# ZX_UNO_0_15.net
KiCad netlist of a schematic drawn in Altium Designer
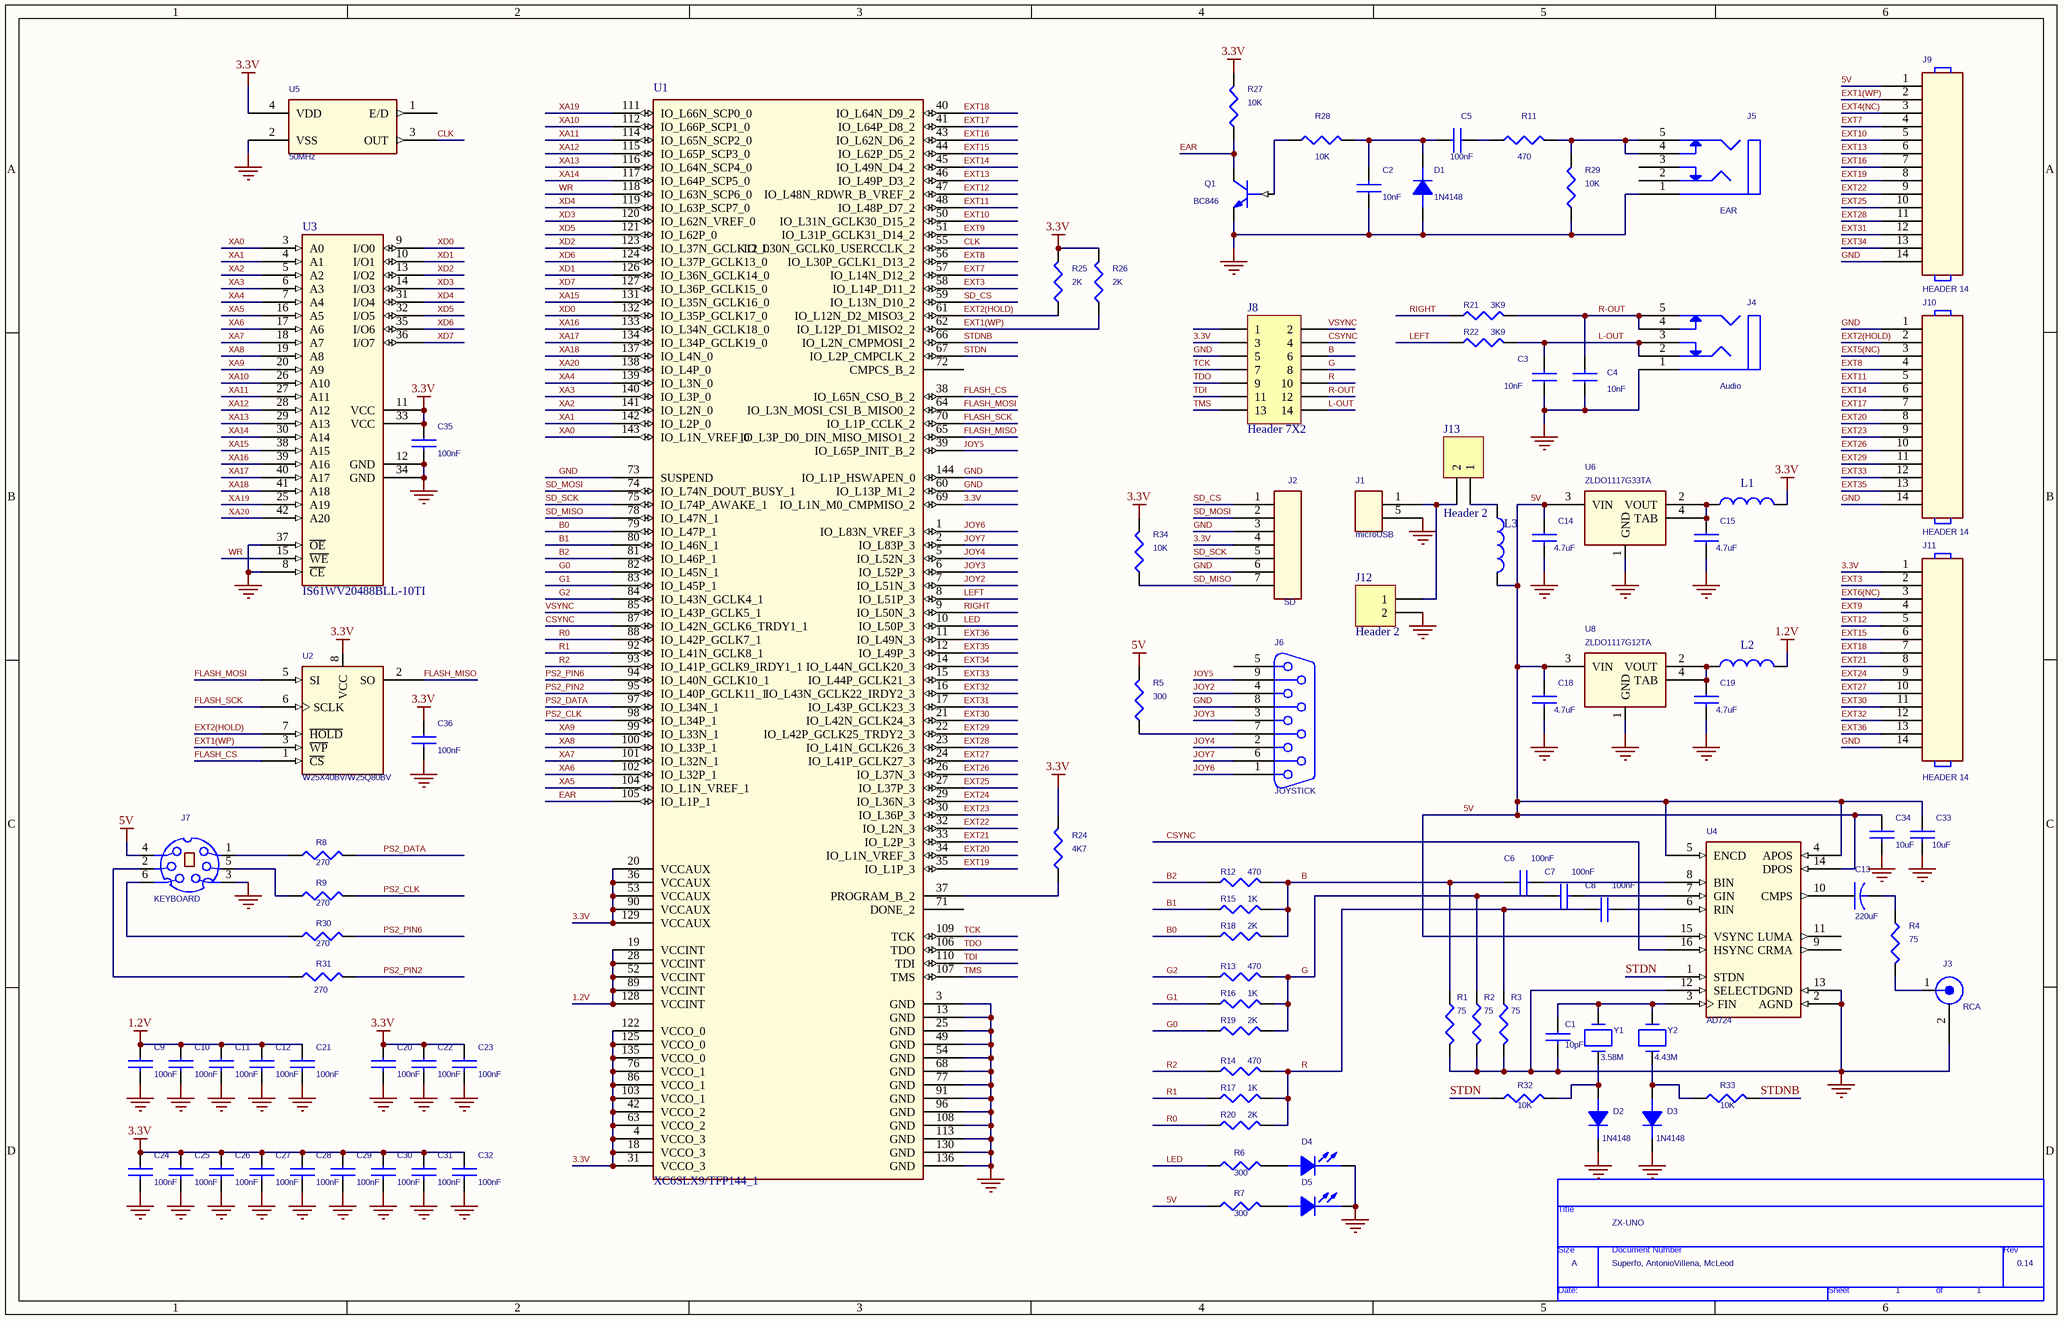
[diagram p0: ZX_UNO_0_15.SchDoc]

(export (version "E")
  (design (tool "Eeschema 10.0.6"))
  (components
    (comp (ref "*")
      (value "TitleBlock0")
      (fields
        (field (name "PAGE COUNT") "1")
        (field (name "PAGE NUMBER") "1")
        (field (name "PAGE SIZE") "A")
        (field (name "TITLE") "ZX-UNO")
        (field (name "REVCODE") "0.14")
        (field (name "DOC") "Superfo, AntonioVillena, McLeod")
      )
      (libsource (lib "*") (part "TitleBlock0"))
    )
    (comp (ref "C1") (value "10pF") (libsource (lib "*") (part "CAP NP_Dup1")))
    (comp (ref "C2") (value "10nF") (libsource (lib "*") (part "CAP NP_Dup1")))
    (comp (ref "C3") (value "10nF") (libsource (lib "*") (part "CAP NP_Dup1")))
    (comp (ref "C4") (value "10nF") (libsource (lib "*") (part "CAP NP_Dup1")))
    (comp (ref "C5") (value "100nF") (libsource (lib "*") (part "CAP NP_Dup1")))
    (comp (ref "C6") (value "100nF") (libsource (lib "*") (part "CAP NP_Dup1")))
    (comp (ref "C7") (value "100nF") (libsource (lib "*") (part "CAP NP_Dup1")))
    (comp (ref "C8") (value "100nF") (libsource (lib "*") (part "CAP NP_Dup1")))
    (comp (ref "C9") (value "100nF") (libsource (lib "*") (part "CAP NP")))
    (comp (ref "C10") (value "100nF") (libsource (lib "*") (part "CAP NP")))
    (comp (ref "C11") (value "100nF") (libsource (lib "*") (part "CAP NP")))
    (comp (ref "C12") (value "100nF") (libsource (lib "*") (part "CAP NP")))
    (comp (ref "C13") (value "220uF") (libsource (lib "*") (part "CAP")))
    (comp (ref "C14") (value "4.7uF") (libsource (lib "*") (part "CAP NP")))
    (comp (ref "C15") (value "4.7uF") (libsource (lib "*") (part "CAP NP")))
    (comp (ref "C18") (value "4.7uF") (libsource (lib "*") (part "CAP NP")))
    (comp (ref "C19") (value "4.7uF") (libsource (lib "*") (part "CAP NP")))
    (comp (ref "C20") (value "100nF") (libsource (lib "*") (part "CAP NP")))
    (comp (ref "C21") (value "100nF") (libsource (lib "*") (part "CAP NP")))
    (comp (ref "C22") (value "100nF") (libsource (lib "*") (part "CAP NP")))
    (comp (ref "C23") (value "100nF") (libsource (lib "*") (part "CAP NP")))
    (comp (ref "C24") (value "100nF") (libsource (lib "*") (part "CAP NP")))
    (comp (ref "C25") (value "100nF") (libsource (lib "*") (part "CAP NP")))
    (comp (ref "C26") (value "100nF") (libsource (lib "*") (part "CAP NP")))
    (comp (ref "C27") (value "100nF") (libsource (lib "*") (part "CAP NP")))
    (comp (ref "C28") (value "100nF") (libsource (lib "*") (part "CAP NP")))
    (comp (ref "C29") (value "100nF") (libsource (lib "*") (part "CAP NP")))
    (comp (ref "C30") (value "100nF") (libsource (lib "*") (part "CAP NP")))
    (comp (ref "C31") (value "100nF") (libsource (lib "*") (part "CAP NP")))
    (comp (ref "C32") (value "100nF") (libsource (lib "*") (part "CAP NP")))
    (comp (ref "C33") (value "10uF") (libsource (lib "*") (part "CAP NP")))
    (comp (ref "C34") (value "10uF") (libsource (lib "*") (part "CAP NP")))
    (comp (ref "C35") (value "100nF") (libsource (lib "*") (part "CAP NP")))
    (comp (ref "C36") (value "100nF") (libsource (lib "*") (part "CAP NP")))
    (comp (ref "D1") (value "1N4148") (libsource (lib "*") (part "DIODE")))
    (comp (ref "D2") (value "1N4148") (libsource (lib "*") (part "DIODE")))
    (comp (ref "D3") (value "1N4148") (libsource (lib "*") (part "DIODE")))
    (comp (ref "D4") (value "LED") (libsource (lib "*") (part "LED")))
    (comp (ref "D5") (value "LED") (libsource (lib "*") (part "LED")))
    (comp (ref "J1") (value "microUSB") (libsource (lib "*") (part "CON2_0")))
    (comp (ref "J2") (value "SD") (libsource (lib "*") (part "CON7")))
    (comp (ref "J3") (value "RCA") (libsource (lib "*") (part "RCA JACK")))
    (comp (ref "J4")
      (value "Audio")
      (footprint "AUDIO JACK PSG01538 - duplicate")
      (libsource (lib "*") (part "PHONEJACK STEREO SW_0"))
    )
    (comp (ref "J5") (value "EAR") (libsource (lib "*") (part "PHONEJACK STEREO SW_0")))
    (comp (ref "J6") (value "JOYSTICK") (libsource (lib "*") (part "CONNECTOR DB9")))
    (comp (ref "J7") (value "KEYBOARD") (libsource (lib "*") (part "M-DIN_0")))
    (comp (ref "J8")
      (value "Header 7X2")
      (footprint "HDR2X7")
      (description "Header, 7-Pin, Dual row")
      (fields (field (name "PUBLISHER") "Altium Limited"))
      (libsource (lib "Miscellaneous Connectors") (part "Header 7X2"))
    )
    (comp (ref "J9") (value "HEADER 14") (libsource (lib "*") (part "HEADER 14")))
    (comp (ref "J10") (value "HEADER 14") (libsource (lib "*") (part "HEADER 14")))
    (comp (ref "J11") (value "HEADER 14") (libsource (lib "*") (part "HEADER 14")))
    (comp (ref "J12")
      (value "Header 2")
      (footprint "HDR1X2")
      (description "Header, 2-Pin")
      (fields (field (name "PUBLISHER") "Altium Limited"))
      (libsource (lib "Miscellaneous Connectors") (part "Header 2"))
    )
    (comp (ref "J13")
      (value "Header 2")
      (footprint "HDR1X2")
      (description "Header, 2-Pin")
      (fields (field (name "PUBLISHER") "Altium Limited"))
      (libsource (lib "") (part "Header 2_1"))
    )
    (comp (ref "L1")
      (value "Inductor")
      (footprint "SM/L_0805")
      (fields (field (name "PUBLISHER") "Altium Limited"))
      (libsource (lib "Miscellaneous Devices") (part "Inductor"))
    )
    (comp (ref "L2")
      (value "Inductor")
      (footprint "SM/L_0805")
      (fields (field (name "PUBLISHER") "Altium Limited"))
      (libsource (lib "Miscellaneous Devices") (part "Inductor"))
    )
    (comp (ref "L3")
      (value "Inductor")
      (footprint "SM/L_0805")
      (fields (field (name "PUBLISHER") "Altium Limited"))
      (libsource (lib "Miscellaneous Devices") (part "Inductor"))
    )
    (comp (ref "Q1") (value "BC846") (libsource (lib "*") (part "BC547")))
    (comp (ref "R1") (value "75") (libsource (lib "*") (part "R")))
    (comp (ref "R2") (value "75") (libsource (lib "*") (part "R")))
    (comp (ref "R3") (value "75") (libsource (lib "*") (part "R")))
    (comp (ref "R4") (value "75") (libsource (lib "*") (part "R")))
    (comp (ref "R5") (value "300") (libsource (lib "*") (part "R")))
    (comp (ref "R6") (value "300") (libsource (lib "*") (part "R")))
    (comp (ref "R7") (value "300") (libsource (lib "*") (part "R")))
    (comp (ref "R8") (value "270") (libsource (lib "*") (part "R")))
    (comp (ref "R9") (value "270") (libsource (lib "*") (part "R")))
    (comp (ref "R11") (value "470") (libsource (lib "*") (part "R")))
    (comp (ref "R12") (value "470") (libsource (lib "*") (part "R")))
    (comp (ref "R13") (value "470") (libsource (lib "*") (part "R")))
    (comp (ref "R14") (value "470") (libsource (lib "*") (part "R")))
    (comp (ref "R15") (value "1K") (libsource (lib "*") (part "R")))
    (comp (ref "R16") (value "1K") (libsource (lib "*") (part "R")))
    (comp (ref "R17") (value "1K") (libsource (lib "*") (part "R")))
    (comp (ref "R18") (value "2K") (libsource (lib "*") (part "R")))
    (comp (ref "R19") (value "2K") (libsource (lib "*") (part "R")))
    (comp (ref "R20") (value "2K") (libsource (lib "*") (part "R")))
    (comp (ref "R21") (value "3K9") (libsource (lib "*") (part "R")))
    (comp (ref "R22") (value "3K9") (libsource (lib "*") (part "R")))
    (comp (ref "R24") (value "4K7") (libsource (lib "*") (part "R")))
    (comp (ref "R25") (value "2K") (libsource (lib "*") (part "R")))
    (comp (ref "R26") (value "2K") (libsource (lib "*") (part "R")))
    (comp (ref "R27") (value "10K") (libsource (lib "*") (part "R")))
    (comp (ref "R28") (value "10K") (libsource (lib "*") (part "R")))
    (comp (ref "R29") (value "10K") (libsource (lib "*") (part "R")))
    (comp (ref "R30") (value "270") (libsource (lib "*") (part "R")))
    (comp (ref "R31") (value "270") (libsource (lib "*") (part "R")))
    (comp (ref "R32") (value "10K") (libsource (lib "*") (part "R")))
    (comp (ref "R33") (value "10K") (libsource (lib "*") (part "R")))
    (comp (ref "R34") (value "10K") (libsource (lib "*") (part "R")))
    (comp (ref "U1")
      (value "XC6SLX9/TFP144_1")
      (libsource (lib "ZX_UNO_0_13_Library") (part "XC6SLX9/TFP144_1"))
    )
    (comp (ref "U2") (value "W25X40BV/W25Q80BV") (libsource (lib "*") (part "AT45DB011/SOIC_3")))
    (comp (ref "U3")
      (value "IS61WV20488BLL-10TI")
      (footprint "SOP80P1176-44M")
      (libsource (lib "ZX_UNO_Library") (part "IS61WV20488BLL-10TI"))
    )
    (comp (ref "U4") (value "AD724") (libsource (lib "*") (part "AD724")))
    (comp (ref "U5") (value "50MHz") (libsource (lib "*") (part "CS-403/TO_0")))
    (comp (ref "U6")
      (value "ZLDO1117G33TA")
      (footprint "SM/SOT223")
      (libsource (lib "*") (part "REGULATOR-1_0"))
    )
    (comp (ref "U8")
      (value "ZLDO1117G12TA")
      (footprint "SM/SOT223")
      (libsource (lib "*") (part "REGULATOR-1_0"))
    )
    (comp (ref "Y1") (value "3.58M") (libsource (lib "*") (part "CRYSTAL")))
    (comp (ref "Y2") (value "4.43M") (libsource (lib "*") (part "CRYSTAL")))
  )
  (nets
    (net (code "1") (name "/B") (class "Default")
      (node (ref "C6") (pin "1") (pinfunction "1_1") (pintype "passive"))
      (node (ref "J8") (pin "6") (pinfunction "6_6") (pintype "passive"))
      (node (ref "R1") (pin "1") (pinfunction "1_1") (pintype "passive"))
      (node (ref "R12") (pin "2") (pinfunction "2_2") (pintype "passive"))
      (node (ref "R15") (pin "2") (pinfunction "2_2") (pintype "passive"))
      (node (ref "R18") (pin "2") (pinfunction "2_2") (pintype "passive"))
    )
    (net (code "2") (name "/B0") (class "Default")
      (node (ref "R18") (pin "1") (pinfunction "1_1") (pintype "passive"))
      (node (ref "U1") (pin "79") (pinfunction "IO_L47P_1_79") (pintype "bidirectional"))
    )
    (net (code "3") (name "/B1") (class "Default")
      (node (ref "R15") (pin "1") (pinfunction "1_1") (pintype "passive"))
      (node (ref "U1") (pin "80") (pinfunction "IO_L46N_1_80") (pintype "bidirectional"))
    )
    (net (code "4") (name "/B2") (class "Default")
      (node (ref "R12") (pin "1") (pinfunction "1_1") (pintype "passive"))
      (node (ref "U1") (pin "81") (pinfunction "IO_L46P_1_81") (pintype "bidirectional"))
    )
    (net (code "5") (name "/CLK") (class "Default")
      (node (ref "U1") (pin "55") (pinfunction "IO_L30N_GCLK0_USERCCLK_2_55") (pintype "bidirectional"))
      (node (ref "U5") (pin "3") (pinfunction "OUT_3") (pintype "output"))
    )
    (net (code "6") (name "/CSYNC") (class "Default")
      (node (ref "J8") (pin "4") (pinfunction "4_4") (pintype "passive"))
      (node (ref "U1") (pin "87") (pinfunction "IO_L42N_GCLK6_TRDY1_1_87") (pintype "bidirectional"))
      (node (ref "U4") (pin "16") (pinfunction "HSYNC_16") (pintype "input"))
    )
    (net (code "7") (name "/EAR") (class "Default")
      (node (ref "Q1") (pin "1") (pinfunction "COLLECTOR_1") (pintype "passive"))
      (node (ref "R27") (pin "2") (pinfunction "2_2") (pintype "passive"))
      (node (ref "U1") (pin "105") (pinfunction "IO_L1P_1_105") (pintype "bidirectional"))
    )
    (net (code "8") (name "/EXT1(WP)") (class "Default")
      (node (ref "J9") (pin "2") (pinfunction "2_2") (pintype "passive"))
      (node (ref "R26") (pin "1") (pinfunction "1_1") (pintype "passive"))
      (node (ref "U1") (pin "62") (pinfunction "IO_L12P_D1_MISO2_2_62") (pintype "bidirectional"))
      (node (ref "U2") (pin "3") (pinfunction "~{WP}_3") (pintype "input"))
    )
    (net (code "9") (name "/EXT2(HOLD)") (class "Default")
      (node (ref "J10") (pin "2") (pinfunction "2_2") (pintype "passive"))
      (node (ref "R25") (pin "1") (pinfunction "1_1") (pintype "passive"))
      (node (ref "U1") (pin "61") (pinfunction "IO_L12N_D2_MISO3_2_61") (pintype "bidirectional"))
      (node (ref "U2") (pin "7") (pinfunction "~{HOLD}_7") (pintype "input"))
    )
    (net (code "10") (name "/EXT3") (class "Default")
      (node (ref "J11") (pin "2") (pinfunction "2_2") (pintype "passive"))
      (node (ref "U1") (pin "58") (pinfunction "IO_L14P_D11_2_58") (pintype "bidirectional"))
    )
    (net (code "11") (name "/EXT4(NC)") (class "Default")
      (node (ref "J9") (pin "3") (pinfunction "3_3") (pintype "passive"))
    )
    (net (code "12") (name "/EXT5(NC)") (class "Default")
      (node (ref "J10") (pin "3") (pinfunction "3_3") (pintype "passive"))
    )
    (net (code "13") (name "/EXT6(NC)") (class "Default")
      (node (ref "J11") (pin "3") (pinfunction "3_3") (pintype "passive"))
    )
    (net (code "14") (name "/EXT7") (class "Default")
      (node (ref "J9") (pin "4") (pinfunction "4_4") (pintype "passive"))
      (node (ref "U1") (pin "57") (pinfunction "IO_L14N_D12_2_57") (pintype "bidirectional"))
    )
    (net (code "15") (name "/EXT8") (class "Default")
      (node (ref "J10") (pin "4") (pinfunction "4_4") (pintype "passive"))
      (node (ref "U1") (pin "56") (pinfunction "IO_L30P_GCLK1_D13_2_56") (pintype "bidirectional"))
    )
    (net (code "16") (name "/EXT9") (class "Default")
      (node (ref "J11") (pin "4") (pinfunction "4_4") (pintype "passive"))
      (node (ref "U1") (pin "51") (pinfunction "IO_L31P_GCLK31_D14_2_51") (pintype "bidirectional"))
    )
    (net (code "17") (name "/EXT10") (class "Default")
      (node (ref "J9") (pin "5") (pinfunction "5_5") (pintype "passive"))
      (node (ref "U1") (pin "50") (pinfunction "IO_L31N_GCLK30_D15_2_50") (pintype "bidirectional"))
    )
    (net (code "18") (name "/EXT11") (class "Default")
      (node (ref "J10") (pin "5") (pinfunction "5_5") (pintype "passive"))
      (node (ref "U1") (pin "48") (pinfunction "IO_L48P_D7_2_48") (pintype "bidirectional"))
    )
    (net (code "19") (name "/EXT12") (class "Default")
      (node (ref "J11") (pin "5") (pinfunction "5_5") (pintype "passive"))
      (node (ref "U1") (pin "47") (pinfunction "IO_L48N_RDWR_B_VREF_2_47") (pintype "bidirectional"))
    )
    (net (code "20") (name "/EXT13") (class "Default")
      (node (ref "J9") (pin "6") (pinfunction "6_6") (pintype "passive"))
      (node (ref "U1") (pin "46") (pinfunction "IO_L49P_D3_2_46") (pintype "bidirectional"))
    )
    (net (code "21") (name "/EXT14") (class "Default")
      (node (ref "J10") (pin "6") (pinfunction "6_6") (pintype "passive"))
      (node (ref "U1") (pin "45") (pinfunction "IO_L49N_D4_2_45") (pintype "bidirectional"))
    )
    (net (code "22") (name "/EXT15") (class "Default")
      (node (ref "J11") (pin "6") (pinfunction "6_6") (pintype "passive"))
      (node (ref "U1") (pin "44") (pinfunction "IO_L62P_D5_2_44") (pintype "bidirectional"))
    )
    (net (code "23") (name "/EXT16") (class "Default")
      (node (ref "J9") (pin "7") (pinfunction "7_7") (pintype "passive"))
      (node (ref "U1") (pin "43") (pinfunction "IO_L62N_D6_2_43") (pintype "bidirectional"))
    )
    (net (code "24") (name "/EXT17") (class "Default")
      (node (ref "J10") (pin "7") (pinfunction "7_7") (pintype "passive"))
      (node (ref "U1") (pin "41") (pinfunction "IO_L64P_D8_2_41") (pintype "bidirectional"))
    )
    (net (code "25") (name "/EXT18") (class "Default")
      (node (ref "J11") (pin "7") (pinfunction "7_7") (pintype "passive"))
      (node (ref "U1") (pin "40") (pinfunction "IO_L64N_D9_2_40") (pintype "bidirectional"))
    )
    (net (code "26") (name "/EXT19") (class "Default")
      (node (ref "J9") (pin "8") (pinfunction "8_8") (pintype "passive"))
      (node (ref "U1") (pin "35") (pinfunction "IO_L1P_3_35") (pintype "bidirectional"))
    )
    (net (code "27") (name "/EXT20") (class "Default")
      (node (ref "J10") (pin "8") (pinfunction "8_8") (pintype "passive"))
      (node (ref "U1") (pin "34") (pinfunction "IO_L1N_VREF_3_34") (pintype "bidirectional"))
    )
    (net (code "28") (name "/EXT21") (class "Default")
      (node (ref "J11") (pin "8") (pinfunction "8_8") (pintype "passive"))
      (node (ref "U1") (pin "33") (pinfunction "IO_L2P_3_33") (pintype "bidirectional"))
    )
    (net (code "29") (name "/EXT22") (class "Default")
      (node (ref "J9") (pin "9") (pinfunction "9_9") (pintype "passive"))
      (node (ref "U1") (pin "32") (pinfunction "IO_L2N_3_32") (pintype "bidirectional"))
    )
    (net (code "30") (name "/EXT23") (class "Default")
      (node (ref "J10") (pin "9") (pinfunction "9_9") (pintype "passive"))
      (node (ref "U1") (pin "30") (pinfunction "IO_L36P_3_30") (pintype "bidirectional"))
    )
    (net (code "31") (name "/EXT24") (class "Default")
      (node (ref "J11") (pin "9") (pinfunction "9_9") (pintype "passive"))
      (node (ref "U1") (pin "29") (pinfunction "IO_L36N_3_29") (pintype "bidirectional"))
    )
    (net (code "32") (name "/EXT25") (class "Default")
      (node (ref "J9") (pin "10") (pinfunction "10_10") (pintype "passive"))
      (node (ref "U1") (pin "27") (pinfunction "IO_L37P_3_27") (pintype "bidirectional"))
    )
    (net (code "33") (name "/EXT26") (class "Default")
      (node (ref "J10") (pin "10") (pinfunction "10_10") (pintype "passive"))
      (node (ref "U1") (pin "26") (pinfunction "IO_L37N_3_26") (pintype "bidirectional"))
    )
    (net (code "34") (name "/EXT27") (class "Default")
      (node (ref "J11") (pin "10") (pinfunction "10_10") (pintype "passive"))
      (node (ref "U1") (pin "24") (pinfunction "IO_L41P_GCLK27_3_24") (pintype "bidirectional"))
    )
    (net (code "35") (name "/EXT28") (class "Default")
      (node (ref "J9") (pin "11") (pinfunction "11_11") (pintype "passive"))
      (node (ref "U1") (pin "23") (pinfunction "IO_L41N_GCLK26_3_23") (pintype "bidirectional"))
    )
    (net (code "36") (name "/EXT29") (class "Default")
      (node (ref "J10") (pin "11") (pinfunction "11_11") (pintype "passive"))
      (node (ref "U1") (pin "22") (pinfunction "IO_L42P_GCLK25_TRDY2_3_22") (pintype "bidirectional"))
    )
    (net (code "37") (name "/EXT30") (class "Default")
      (node (ref "J11") (pin "11") (pinfunction "11_11") (pintype "passive"))
      (node (ref "U1") (pin "21") (pinfunction "IO_L42N_GCLK24_3_21") (pintype "bidirectional"))
    )
    (net (code "38") (name "/EXT31") (class "Default")
      (node (ref "J9") (pin "12") (pinfunction "12_12") (pintype "passive"))
      (node (ref "U1") (pin "17") (pinfunction "IO_L43P_GCLK23_3_17") (pintype "bidirectional"))
    )
    (net (code "39") (name "/EXT32") (class "Default")
      (node (ref "J11") (pin "12") (pinfunction "12_12") (pintype "passive"))
      (node (ref "U1") (pin "16") (pinfunction "IO_L43N_GCLK22_IRDY2_3_16") (pintype "bidirectional"))
    )
    (net (code "40") (name "/EXT33") (class "Default")
      (node (ref "J10") (pin "12") (pinfunction "12_12") (pintype "passive"))
      (node (ref "U1") (pin "15") (pinfunction "IO_L44P_GCLK21_3_15") (pintype "bidirectional"))
    )
    (net (code "41") (name "/EXT34") (class "Default")
      (node (ref "J9") (pin "13") (pinfunction "13_13") (pintype "passive"))
      (node (ref "U1") (pin "14") (pinfunction "IO_L44N_GCLK20_3_14") (pintype "bidirectional"))
    )
    (net (code "42") (name "/EXT35") (class "Default")
      (node (ref "J10") (pin "13") (pinfunction "13_13") (pintype "passive"))
      (node (ref "U1") (pin "12") (pinfunction "IO_L49P_3_12") (pintype "bidirectional"))
    )
    (net (code "43") (name "/EXT36") (class "Default")
      (node (ref "J11") (pin "13") (pinfunction "13_13") (pintype "passive"))
      (node (ref "U1") (pin "11") (pinfunction "IO_L49N_3_11") (pintype "bidirectional"))
    )
    (net (code "44") (name "/FLASH_CS") (class "Default")
      (node (ref "U1") (pin "38") (pinfunction "IO_L65N_CSO_B_2_38") (pintype "bidirectional"))
      (node (ref "U2") (pin "1") (pinfunction "~{CS}_1") (pintype "input"))
    )
    (net (code "45") (name "/FLASH_MISO") (class "Default")
      (node (ref "U1") (pin "65") (pinfunction "IO_L3P_D0_DIN_MISO_MISO1_2_65") (pintype "bidirectional"))
      (node (ref "U2") (pin "2") (pinfunction "SO_2") (pintype "tri_state"))
    )
    (net (code "46") (name "/FLASH_MOSI") (class "Default")
      (node (ref "U1") (pin "64") (pinfunction "IO_L3N_MOSI_CSI_B_MISO0_2_64") (pintype "bidirectional"))
      (node (ref "U2") (pin "5") (pinfunction "SI_5") (pintype "input"))
    )
    (net (code "47") (name "/FLASH_SCK") (class "Default")
      (node (ref "U1") (pin "70") (pinfunction "IO_L1P_CCLK_2_70") (pintype "bidirectional"))
      (node (ref "U2") (pin "6") (pinfunction "SCLK_6") (pintype "input"))
    )
    (net (code "48") (name "/G") (class "Default")
      (node (ref "C7") (pin "1") (pinfunction "1_1") (pintype "passive"))
      (node (ref "J8") (pin "8") (pinfunction "8_8") (pintype "passive"))
      (node (ref "R13") (pin "2") (pinfunction "2_2") (pintype "passive"))
      (node (ref "R16") (pin "2") (pinfunction "2_2") (pintype "passive"))
      (node (ref "R19") (pin "2") (pinfunction "2_2") (pintype "passive"))
      (node (ref "R2") (pin "1") (pinfunction "1_1") (pintype "passive"))
    )
    (net (code "49") (name "/G0") (class "Default")
      (node (ref "R19") (pin "1") (pinfunction "1_1") (pintype "passive"))
      (node (ref "U1") (pin "82") (pinfunction "IO_L45N_1_82") (pintype "bidirectional"))
    )
    (net (code "50") (name "/G1") (class "Default")
      (node (ref "R16") (pin "1") (pinfunction "1_1") (pintype "passive"))
      (node (ref "U1") (pin "83") (pinfunction "IO_L45P_1_83") (pintype "bidirectional"))
    )
    (net (code "51") (name "/G2") (class "Default")
      (node (ref "R13") (pin "1") (pinfunction "1_1") (pintype "passive"))
      (node (ref "U1") (pin "84") (pinfunction "IO_L43N_GCLK4_1_84") (pintype "bidirectional"))
    )
    (net (code "52") (name "/JOY2") (class "Default")
      (node (ref "J6") (pin "4") (pinfunction "4_4") (pintype "passive"))
      (node (ref "U1") (pin "7") (pinfunction "IO_L51N_3_7") (pintype "bidirectional"))
    )
    (net (code "53") (name "/JOY3") (class "Default")
      (node (ref "J6") (pin "3") (pinfunction "3_3") (pintype "passive"))
      (node (ref "U1") (pin "6") (pinfunction "IO_L52P_3_6") (pintype "bidirectional"))
    )
    (net (code "54") (name "/JOY4") (class "Default")
      (node (ref "J6") (pin "2") (pinfunction "2_2") (pintype "passive"))
      (node (ref "U1") (pin "5") (pinfunction "IO_L52N_3_5") (pintype "bidirectional"))
    )
    (net (code "55") (name "/JOY5") (class "Default")
      (node (ref "J6") (pin "9") (pinfunction "9_9") (pintype "passive"))
      (node (ref "U1") (pin "39") (pinfunction "IO_L65P_INIT_B_2_39") (pintype "bidirectional"))
    )
    (net (code "56") (name "/JOY6") (class "Default")
      (node (ref "J6") (pin "1") (pinfunction "1_1") (pintype "passive"))
      (node (ref "U1") (pin "1") (pinfunction "IO_L83N_VREF_3_1") (pintype "bidirectional"))
    )
    (net (code "57") (name "/JOY7") (class "Default")
      (node (ref "J6") (pin "6") (pinfunction "6_6") (pintype "passive"))
      (node (ref "U1") (pin "2") (pinfunction "IO_L83P_3_2") (pintype "bidirectional"))
    )
    (net (code "58") (name "/L-OUT") (class "Default")
      (node (ref "C3") (pin "2") (pinfunction "2_2") (pintype "passive"))
      (node (ref "J4") (pin "2") (pinfunction "D_2") (pintype "passive"))
      (node (ref "J4") (pin "3") (pinfunction "C_3") (pintype "passive"))
      (node (ref "J8") (pin "14") (pinfunction "14_14") (pintype "passive"))
      (node (ref "R22") (pin "2") (pinfunction "2_2") (pintype "passive"))
    )
    (net (code "59") (name "/LED") (class "Default")
      (node (ref "R6") (pin "1") (pinfunction "1_1") (pintype "passive"))
      (node (ref "U1") (pin "10") (pinfunction "IO_L50P_3_10") (pintype "bidirectional"))
    )
    (net (code "60") (name "/LEFT") (class "Default")
      (node (ref "R22") (pin "1") (pinfunction "1_1") (pintype "passive"))
      (node (ref "U1") (pin "8") (pinfunction "IO_L51P_3_8") (pintype "bidirectional"))
    )
    (net (code "61") (name "/PS2_CLK") (class "Default")
      (node (ref "R9") (pin "2") (pinfunction "2_2") (pintype "passive"))
      (node (ref "U1") (pin "98") (pinfunction "IO_L34P_1_98") (pintype "bidirectional"))
    )
    (net (code "62") (name "/PS2_DATA") (class "Default")
      (node (ref "R8") (pin "2") (pinfunction "2_2") (pintype "passive"))
      (node (ref "U1") (pin "97") (pinfunction "IO_L34N_1_97") (pintype "bidirectional"))
    )
    (net (code "63") (name "/PS2_PIN2") (class "Default")
      (node (ref "R31") (pin "2") (pinfunction "2_2") (pintype "passive"))
      (node (ref "U1") (pin "95") (pinfunction "IO_L40P_GCLK11_1_95") (pintype "bidirectional"))
    )
    (net (code "64") (name "/PS2_PIN6") (class "Default")
      (node (ref "R30") (pin "2") (pinfunction "2_2") (pintype "passive"))
      (node (ref "U1") (pin "94") (pinfunction "IO_L40N_GCLK10_1_94") (pintype "bidirectional"))
    )
    (net (code "65") (name "/R") (class "Default")
      (node (ref "C8") (pin "1") (pinfunction "1_1") (pintype "passive"))
      (node (ref "J8") (pin "10") (pinfunction "10_10") (pintype "passive"))
      (node (ref "R14") (pin "2") (pinfunction "2_2") (pintype "passive"))
      (node (ref "R17") (pin "2") (pinfunction "2_2") (pintype "passive"))
      (node (ref "R20") (pin "2") (pinfunction "2_2") (pintype "passive"))
      (node (ref "R3") (pin "1") (pinfunction "1_1") (pintype "passive"))
    )
    (net (code "66") (name "/R-OUT") (class "Default")
      (node (ref "C4") (pin "2") (pinfunction "2_2") (pintype "passive"))
      (node (ref "J4") (pin "4") (pinfunction "B_4") (pintype "passive"))
      (node (ref "J4") (pin "5") (pinfunction "A_5") (pintype "passive"))
      (node (ref "J8") (pin "12") (pinfunction "12_12") (pintype "passive"))
      (node (ref "R21") (pin "2") (pinfunction "2_2") (pintype "passive"))
    )
    (net (code "67") (name "/R0") (class "Default")
      (node (ref "R20") (pin "1") (pinfunction "1_1") (pintype "passive"))
      (node (ref "U1") (pin "88") (pinfunction "IO_L42P_GCLK7_1_88") (pintype "bidirectional"))
    )
    (net (code "68") (name "/R1") (class "Default")
      (node (ref "R17") (pin "1") (pinfunction "1_1") (pintype "passive"))
      (node (ref "U1") (pin "92") (pinfunction "IO_L41N_GCLK8_1_92") (pintype "bidirectional"))
    )
    (net (code "69") (name "/R2") (class "Default")
      (node (ref "R14") (pin "1") (pinfunction "1_1") (pintype "passive"))
      (node (ref "U1") (pin "93") (pinfunction "IO_L41P_GCLK9_IRDY1_1_93") (pintype "bidirectional"))
    )
    (net (code "70") (name "/RIGHT") (class "Default")
      (node (ref "R21") (pin "1") (pinfunction "1_1") (pintype "passive"))
      (node (ref "U1") (pin "9") (pinfunction "IO_L50N_3_9") (pintype "bidirectional"))
    )
    (net (code "71") (name "/SD_CS") (class "Default")
      (node (ref "J2") (pin "1") (pinfunction "1_1") (pintype "passive"))
      (node (ref "U1") (pin "59") (pinfunction "IO_L13N_D10_2_59") (pintype "bidirectional"))
    )
    (net (code "72") (name "/SD_MISO") (class "Default")
      (node (ref "J2") (pin "7") (pinfunction "7_7") (pintype "passive"))
      (node (ref "R34") (pin "1") (pinfunction "1_1") (pintype "passive"))
      (node (ref "U1") (pin "78") (pinfunction "IO_L47N_1_78") (pintype "bidirectional"))
    )
    (net (code "73") (name "/SD_MOSI") (class "Default")
      (node (ref "J2") (pin "2") (pinfunction "2_2") (pintype "passive"))
      (node (ref "U1") (pin "74") (pinfunction "IO_L74N_DOUT_BUSY_1_74") (pintype "bidirectional"))
    )
    (net (code "74") (name "/SD_SCK") (class "Default")
      (node (ref "J2") (pin "5") (pinfunction "5_5") (pintype "passive"))
      (node (ref "U1") (pin "75") (pinfunction "IO_L74P_AWAKE_1_75") (pintype "bidirectional"))
    )
    (net (code "75") (name "/STDN") (class "Default")
      (node (ref "R32") (pin "1") (pinfunction "1_1") (pintype "passive"))
      (node (ref "U1") (pin "67") (pinfunction "IO_L2P_CMPCLK_2_67") (pintype "bidirectional"))
      (node (ref "U4") (pin "1") (pinfunction "STDN_1") (pintype "input"))
    )
    (net (code "76") (name "/STDNB") (class "Default")
      (node (ref "R33") (pin "2") (pinfunction "2_2") (pintype "passive"))
      (node (ref "U1") (pin "66") (pinfunction "IO_L2N_CMPMOSI_2_66") (pintype "bidirectional"))
    )
    (net (code "77") (name "/TCK") (class "Default")
      (node (ref "J8") (pin "7") (pinfunction "7_7") (pintype "passive"))
      (node (ref "U1") (pin "109") (pinfunction "TCK_109") (pintype "bidirectional"))
    )
    (net (code "78") (name "/TDI") (class "Default")
      (node (ref "J8") (pin "11") (pinfunction "11_11") (pintype "passive"))
      (node (ref "U1") (pin "110") (pinfunction "TDI_110") (pintype "bidirectional"))
    )
    (net (code "79") (name "/TDO") (class "Default")
      (node (ref "J8") (pin "9") (pinfunction "9_9") (pintype "passive"))
      (node (ref "U1") (pin "106") (pinfunction "TDO_106") (pintype "bidirectional"))
    )
    (net (code "80") (name "/TMS") (class "Default")
      (node (ref "J8") (pin "13") (pinfunction "13_13") (pintype "passive"))
      (node (ref "U1") (pin "107") (pinfunction "TMS_107") (pintype "bidirectional"))
    )
    (net (code "81") (name "/VSYNC") (class "Default")
      (node (ref "J8") (pin "2") (pinfunction "2_2") (pintype "passive"))
      (node (ref "U1") (pin "85") (pinfunction "IO_L43P_GCLK5_1_85") (pintype "bidirectional"))
    )
    (net (code "82") (name "/WR") (class "Default")
      (node (ref "U1") (pin "118") (pinfunction "IO_L63N_SCP6_0_118") (pintype "bidirectional"))
      (node (ref "U3") (pin "15") (pinfunction "~{WE}_15") (pintype "input"))
    )
    (net (code "83") (name "/XA0") (class "Default")
      (node (ref "U1") (pin "143") (pinfunction "IO_L1N_VREF_0_143") (pintype "bidirectional"))
      (node (ref "U3") (pin "3") (pinfunction "A0_3") (pintype "input"))
    )
    (net (code "84") (name "/XA1") (class "Default")
      (node (ref "U1") (pin "142") (pinfunction "IO_L2P_0_142") (pintype "bidirectional"))
      (node (ref "U3") (pin "4") (pinfunction "A1_4") (pintype "input"))
    )
    (net (code "85") (name "/XA2") (class "Default")
      (node (ref "U1") (pin "141") (pinfunction "IO_L2N_0_141") (pintype "bidirectional"))
      (node (ref "U3") (pin "5") (pinfunction "A2_5") (pintype "input"))
    )
    (net (code "86") (name "/XA3") (class "Default")
      (node (ref "U1") (pin "140") (pinfunction "IO_L3P_0_140") (pintype "bidirectional"))
      (node (ref "U3") (pin "6") (pinfunction "A3_6") (pintype "input"))
    )
    (net (code "87") (name "/XA4") (class "Default")
      (node (ref "U1") (pin "139") (pinfunction "IO_L3N_0_139") (pintype "bidirectional"))
      (node (ref "U3") (pin "7") (pinfunction "A4_7") (pintype "input"))
    )
    (net (code "88") (name "/XA5") (class "Default")
      (node (ref "U1") (pin "104") (pinfunction "IO_L1N_VREF_1_104") (pintype "bidirectional"))
      (node (ref "U3") (pin "16") (pinfunction "A5_16") (pintype "input"))
    )
    (net (code "89") (name "/XA6") (class "Default")
      (node (ref "U1") (pin "102") (pinfunction "IO_L32P_1_102") (pintype "bidirectional"))
      (node (ref "U3") (pin "17") (pinfunction "A6_17") (pintype "input"))
    )
    (net (code "90") (name "/XA7") (class "Default")
      (node (ref "U1") (pin "101") (pinfunction "IO_L32N_1_101") (pintype "bidirectional"))
      (node (ref "U3") (pin "18") (pinfunction "A7_18") (pintype "input"))
    )
    (net (code "91") (name "/XA8") (class "Default")
      (node (ref "U1") (pin "100") (pinfunction "IO_L33P_1_100") (pintype "bidirectional"))
      (node (ref "U3") (pin "19") (pinfunction "A8_19") (pintype "input"))
    )
    (net (code "92") (name "/XA9") (class "Default")
      (node (ref "U1") (pin "99") (pinfunction "IO_L33N_1_99") (pintype "bidirectional"))
      (node (ref "U3") (pin "20") (pinfunction "A9_20") (pintype "input"))
    )
    (net (code "93") (name "/XA10") (class "Default")
      (node (ref "U1") (pin "112") (pinfunction "IO_L66P_SCP1_0_112") (pintype "bidirectional"))
      (node (ref "U3") (pin "26") (pinfunction "A10_26") (pintype "input"))
    )
    (net (code "94") (name "/XA11") (class "Default")
      (node (ref "U1") (pin "114") (pinfunction "IO_L65N_SCP2_0_114") (pintype "bidirectional"))
      (node (ref "U3") (pin "27") (pinfunction "A11_27") (pintype "input"))
    )
    (net (code "95") (name "/XA12") (class "Default")
      (node (ref "U1") (pin "115") (pinfunction "IO_L65P_SCP3_0_115") (pintype "bidirectional"))
      (node (ref "U3") (pin "28") (pinfunction "A12_28") (pintype "input"))
    )
    (net (code "96") (name "/XA13") (class "Default")
      (node (ref "U1") (pin "116") (pinfunction "IO_L64N_SCP4_0_116") (pintype "bidirectional"))
      (node (ref "U3") (pin "29") (pinfunction "A13_29") (pintype "input"))
    )
    (net (code "97") (name "/XA14") (class "Default")
      (node (ref "U1") (pin "117") (pinfunction "IO_L64P_SCP5_0_117") (pintype "bidirectional"))
      (node (ref "U3") (pin "30") (pinfunction "A14_30") (pintype "input"))
    )
    (net (code "98") (name "/XA15") (class "Default")
      (node (ref "U1") (pin "131") (pinfunction "IO_L35N_GCLK16_0_131") (pintype "bidirectional"))
      (node (ref "U3") (pin "38") (pinfunction "A15_38") (pintype "input"))
    )
    (net (code "99") (name "/XA16") (class "Default")
      (node (ref "U1") (pin "133") (pinfunction "IO_L34N_GCLK18_0_133") (pintype "bidirectional"))
      (node (ref "U3") (pin "39") (pinfunction "A16_39") (pintype "input"))
    )
    (net (code "100") (name "/XA17") (class "Default")
      (node (ref "U1") (pin "134") (pinfunction "IO_L34P_GCLK19_0_134") (pintype "bidirectional"))
      (node (ref "U3") (pin "40") (pinfunction "A17_40") (pintype "input"))
    )
    (net (code "101") (name "/XA18") (class "Default")
      (node (ref "U1") (pin "137") (pinfunction "IO_L4N_0_137") (pintype "bidirectional"))
      (node (ref "U3") (pin "41") (pinfunction "A18_41") (pintype "input"))
    )
    (net (code "102") (name "/XA19") (class "Default")
      (node (ref "U1") (pin "111") (pinfunction "IO_L66N_SCP0_0_111") (pintype "bidirectional"))
      (node (ref "U3") (pin "25") (pinfunction "A19_25") (pintype "input"))
    )
    (net (code "103") (name "/XA20") (class "Default")
      (node (ref "U1") (pin "138") (pinfunction "IO_L4P_0_138") (pintype "bidirectional"))
      (node (ref "U3") (pin "42") (pinfunction "A20_42") (pintype "input"))
    )
    (net (code "104") (name "/XD0") (class "Default")
      (node (ref "U1") (pin "132") (pinfunction "IO_L35P_GCLK17_0_132") (pintype "bidirectional"))
      (node (ref "U3") (pin "9") (pinfunction "I/O0_9") (pintype "bidirectional"))
    )
    (net (code "105") (name "/XD1") (class "Default")
      (node (ref "U1") (pin "126") (pinfunction "IO_L36N_GCLK14_0_126") (pintype "bidirectional"))
      (node (ref "U3") (pin "10") (pinfunction "I/O1_10") (pintype "bidirectional"))
    )
    (net (code "106") (name "/XD2") (class "Default")
      (node (ref "U1") (pin "123") (pinfunction "IO_L37N_GCLK12_0_123") (pintype "bidirectional"))
      (node (ref "U3") (pin "13") (pinfunction "I/O2_13") (pintype "bidirectional"))
    )
    (net (code "107") (name "/XD3") (class "Default")
      (node (ref "U1") (pin "120") (pinfunction "IO_L62N_VREF_0_120") (pintype "bidirectional"))
      (node (ref "U3") (pin "14") (pinfunction "I/O3_14") (pintype "bidirectional"))
    )
    (net (code "108") (name "/XD4") (class "Default")
      (node (ref "U1") (pin "119") (pinfunction "IO_L63P_SCP7_0_119") (pintype "bidirectional"))
      (node (ref "U3") (pin "31") (pinfunction "I/O4_31") (pintype "bidirectional"))
    )
    (net (code "109") (name "/XD5") (class "Default")
      (node (ref "U1") (pin "121") (pinfunction "IO_L62P_0_121") (pintype "bidirectional"))
      (node (ref "U3") (pin "32") (pinfunction "I/O5_32") (pintype "bidirectional"))
    )
    (net (code "110") (name "/XD6") (class "Default")
      (node (ref "U1") (pin "124") (pinfunction "IO_L37P_GCLK13_0_124") (pintype "bidirectional"))
      (node (ref "U3") (pin "35") (pinfunction "I/O6_35") (pintype "bidirectional"))
    )
    (net (code "111") (name "/XD7") (class "Default")
      (node (ref "U1") (pin "127") (pinfunction "IO_L36P_GCLK15_0_127") (pintype "bidirectional"))
      (node (ref "U3") (pin "36") (pinfunction "I/O7_36") (pintype "bidirectional"))
    )
    (net (code "112") (name "1.2V") (class "Default")
      (node (ref "C10") (pin "1") (pinfunction "1_1") (pintype "passive"))
      (node (ref "C11") (pin "1") (pinfunction "1_1") (pintype "passive"))
      (node (ref "C12") (pin "1") (pinfunction "1_1") (pintype "passive"))
      (node (ref "C21") (pin "1") (pinfunction "1_1") (pintype "passive"))
      (node (ref "C9") (pin "1") (pinfunction "1_1") (pintype "passive"))
      (node (ref "L2") (pin "2") (pinfunction "2_2") (pintype "passive"))
      (node (ref "U1") (pin "128") (pinfunction "VCCINT_128") (pintype "passive"))
      (node (ref "U1") (pin "19") (pinfunction "VCCINT_19") (pintype "passive"))
      (node (ref "U1") (pin "28") (pinfunction "VCCINT_28") (pintype "passive"))
      (node (ref "U1") (pin "52") (pinfunction "VCCINT_52") (pintype "passive"))
      (node (ref "U1") (pin "89") (pinfunction "VCCINT_89") (pintype "passive"))
    )
    (net (code "113") (name "3.3V") (class "Default")
      (node (ref "C20") (pin "1") (pinfunction "1_1") (pintype "passive"))
      (node (ref "C22") (pin "1") (pinfunction "1_1") (pintype "passive"))
      (node (ref "C23") (pin "1") (pinfunction "1_1") (pintype "passive"))
      (node (ref "C24") (pin "1") (pinfunction "1_1") (pintype "passive"))
      (node (ref "C25") (pin "1") (pinfunction "1_1") (pintype "passive"))
      (node (ref "C26") (pin "1") (pinfunction "1_1") (pintype "passive"))
      (node (ref "C27") (pin "1") (pinfunction "1_1") (pintype "passive"))
      (node (ref "C28") (pin "1") (pinfunction "1_1") (pintype "passive"))
      (node (ref "C29") (pin "1") (pinfunction "1_1") (pintype "passive"))
      (node (ref "C30") (pin "1") (pinfunction "1_1") (pintype "passive"))
      (node (ref "C31") (pin "1") (pinfunction "1_1") (pintype "passive"))
      (node (ref "C32") (pin "1") (pinfunction "1_1") (pintype "passive"))
      (node (ref "C35") (pin "1") (pinfunction "1_1") (pintype "passive"))
      (node (ref "C36") (pin "1") (pinfunction "1_1") (pintype "passive"))
      (node (ref "J11") (pin "1") (pinfunction "1_1") (pintype "passive"))
      (node (ref "J2") (pin "4") (pinfunction "4_4") (pintype "passive"))
      (node (ref "J8") (pin "3") (pinfunction "3_3") (pintype "passive"))
      (node (ref "L1") (pin "2") (pinfunction "2_2") (pintype "passive"))
      (node (ref "R24") (pin "2") (pinfunction "2_2") (pintype "passive"))
      (node (ref "R25") (pin "2") (pinfunction "2_2") (pintype "passive"))
      (node (ref "R26") (pin "2") (pinfunction "2_2") (pintype "passive"))
      (node (ref "R27") (pin "1") (pinfunction "1_1") (pintype "passive"))
      (node (ref "R34") (pin "2") (pinfunction "2_2") (pintype "passive"))
      (node (ref "U1") (pin "103") (pinfunction "VCCO_1_103") (pintype "passive"))
      (node (ref "U1") (pin "122") (pinfunction "VCCO_0_122") (pintype "passive"))
      (node (ref "U1") (pin "125") (pinfunction "VCCO_0_125") (pintype "passive"))
      (node (ref "U1") (pin "129") (pinfunction "VCCAUX_129") (pintype "passive"))
      (node (ref "U1") (pin "135") (pinfunction "VCCO_0_135") (pintype "passive"))
      (node (ref "U1") (pin "18") (pinfunction "VCCO_3_18") (pintype "passive"))
      (node (ref "U1") (pin "20") (pinfunction "VCCAUX_20") (pintype "passive"))
      (node (ref "U1") (pin "31") (pinfunction "VCCO_3_31") (pintype "passive"))
      (node (ref "U1") (pin "36") (pinfunction "VCCAUX_36") (pintype "passive"))
      (node (ref "U1") (pin "4") (pinfunction "VCCO_3_4") (pintype "passive"))
      (node (ref "U1") (pin "42") (pinfunction "VCCO_2_42") (pintype "passive"))
      (node (ref "U1") (pin "53") (pinfunction "VCCAUX_53") (pintype "passive"))
      (node (ref "U1") (pin "63") (pinfunction "VCCO_2_63") (pintype "passive"))
      (node (ref "U1") (pin "69") (pinfunction "IO_L1N_M0_CMPMISO_2_69") (pintype "bidirectional"))
      (node (ref "U1") (pin "76") (pinfunction "VCCO_1_76") (pintype "passive"))
      (node (ref "U1") (pin "86") (pinfunction "VCCO_1_86") (pintype "passive"))
      (node (ref "U1") (pin "90") (pinfunction "VCCAUX_90") (pintype "passive"))
      (node (ref "U2") (pin "8") (pinfunction "VCC_8") (pintype "power_in"))
      (node (ref "U3") (pin "11") (pinfunction "VCC_11") (pintype "power_in"))
      (node (ref "U3") (pin "33") (pinfunction "VCC_33") (pintype "power_in"))
      (node (ref "U5") (pin "4") (pinfunction "VDD_4") (pintype "power_in"))
    )
    (net (code "114") (name "5V") (class "Default")
      (node (ref "C14") (pin "1") (pinfunction "1_1") (pintype "passive"))
      (node (ref "C18") (pin "1") (pinfunction "1_1") (pintype "passive"))
      (node (ref "C33") (pin "1") (pinfunction "1_1") (pintype "passive"))
      (node (ref "C34") (pin "1") (pinfunction "1_1") (pintype "passive"))
      (node (ref "J7") (pin "4") (pinfunction "4_4") (pintype "passive"))
      (node (ref "J9") (pin "1") (pinfunction "1_1") (pintype "passive"))
      (node (ref "L3") (pin "2") (pinfunction "2_2") (pintype "passive"))
      (node (ref "R5") (pin "2") (pinfunction "2_2") (pintype "passive"))
      (node (ref "R7") (pin "1") (pinfunction "1_1") (pintype "passive"))
      (node (ref "U4") (pin "14") (pinfunction "DPOS_14") (pintype "input"))
      (node (ref "U4") (pin "15") (pinfunction "VSYNC_15") (pintype "input"))
      (node (ref "U4") (pin "4") (pinfunction "APOS_4") (pintype "input"))
      (node (ref "U4") (pin "5") (pinfunction "ENCD_5") (pintype "input"))
      (node (ref "U6") (pin "3") (pinfunction "VIN_3") (pintype "power_in"))
      (node (ref "U8") (pin "3") (pinfunction "VIN_3") (pintype "power_in"))
    )
    (net (code "115") (name "GND") (class "Default")
      (node (ref "C1") (pin "2") (pinfunction "2_2") (pintype "passive"))
      (node (ref "C10") (pin "2") (pinfunction "2_2") (pintype "passive"))
      (node (ref "C11") (pin "2") (pinfunction "2_2") (pintype "passive"))
      (node (ref "C12") (pin "2") (pinfunction "2_2") (pintype "passive"))
      (node (ref "C14") (pin "2") (pinfunction "2_2") (pintype "passive"))
      (node (ref "C15") (pin "2") (pinfunction "2_2") (pintype "passive"))
      (node (ref "C18") (pin "2") (pinfunction "2_2") (pintype "passive"))
      (node (ref "C19") (pin "2") (pinfunction "2_2") (pintype "passive"))
      (node (ref "C2") (pin "1") (pinfunction "1_1") (pintype "passive"))
      (node (ref "C20") (pin "2") (pinfunction "2_2") (pintype "passive"))
      (node (ref "C21") (pin "2") (pinfunction "2_2") (pintype "passive"))
      (node (ref "C22") (pin "2") (pinfunction "2_2") (pintype "passive"))
      (node (ref "C23") (pin "2") (pinfunction "2_2") (pintype "passive"))
      (node (ref "C24") (pin "2") (pinfunction "2_2") (pintype "passive"))
      (node (ref "C25") (pin "2") (pinfunction "2_2") (pintype "passive"))
      (node (ref "C26") (pin "2") (pinfunction "2_2") (pintype "passive"))
      (node (ref "C27") (pin "2") (pinfunction "2_2") (pintype "passive"))
      (node (ref "C28") (pin "2") (pinfunction "2_2") (pintype "passive"))
      (node (ref "C29") (pin "2") (pinfunction "2_2") (pintype "passive"))
      (node (ref "C3") (pin "1") (pinfunction "1_1") (pintype "passive"))
      (node (ref "C30") (pin "2") (pinfunction "2_2") (pintype "passive"))
      (node (ref "C31") (pin "2") (pinfunction "2_2") (pintype "passive"))
      (node (ref "C32") (pin "2") (pinfunction "2_2") (pintype "passive"))
      (node (ref "C33") (pin "2") (pinfunction "2_2") (pintype "passive"))
      (node (ref "C34") (pin "2") (pinfunction "2_2") (pintype "passive"))
      (node (ref "C35") (pin "2") (pinfunction "2_2") (pintype "passive"))
      (node (ref "C36") (pin "2") (pinfunction "2_2") (pintype "passive"))
      (node (ref "C4") (pin "1") (pinfunction "1_1") (pintype "passive"))
      (node (ref "C9") (pin "2") (pinfunction "2_2") (pintype "passive"))
      (node (ref "D1") (pin "1") (pinfunction "A_1") (pintype "passive"))
      (node (ref "D2") (pin "2") (pinfunction "K_2") (pintype "passive"))
      (node (ref "D3") (pin "2") (pinfunction "K_2") (pintype "passive"))
      (node (ref "D4") (pin "2") (pinfunction "CATHODE_2") (pintype "passive"))
      (node (ref "D5") (pin "2") (pinfunction "CATHODE_2") (pintype "passive"))
      (node (ref "J1") (pin "5") (pinfunction "5_5") (pintype "passive"))
      (node (ref "J10") (pin "1") (pinfunction "1_1") (pintype "passive"))
      (node (ref "J10") (pin "14") (pinfunction "14_14") (pintype "passive"))
      (node (ref "J11") (pin "14") (pinfunction "14_14") (pintype "passive"))
      (node (ref "J12") (pin "2") (pinfunction "2_2") (pintype "passive"))
      (node (ref "J2") (pin "3") (pinfunction "3_3") (pintype "passive"))
      (node (ref "J2") (pin "6") (pinfunction "6_6") (pintype "passive"))
      (node (ref "J3") (pin "2") (pinfunction "SHIELD_2") (pintype "passive"))
      (node (ref "J4") (pin "1") (pinfunction "E_1") (pintype "passive"))
      (node (ref "J5") (pin "1") (pinfunction "E_1") (pintype "passive"))
      (node (ref "J6") (pin "8") (pinfunction "8_8") (pintype "passive"))
      (node (ref "J7") (pin "3") (pinfunction "3_3") (pintype "passive"))
      (node (ref "J7") (pin "M1") (pinfunction "GND_M1") (pintype "power_in"))
      (node (ref "J7") (pin "M2") (pinfunction "GND_M2") (pintype "power_in"))
      (node (ref "J7") (pin "M3") (pinfunction "GND_M3") (pintype "power_in"))
      (node (ref "J8") (pin "5") (pinfunction "5_5") (pintype "passive"))
      (node (ref "J9") (pin "14") (pinfunction "14_14") (pintype "passive"))
      (node (ref "Q1") (pin "3") (pinfunction "EMITTER_3") (pintype "passive"))
      (node (ref "R1") (pin "2") (pinfunction "2_2") (pintype "passive"))
      (node (ref "R2") (pin "2") (pinfunction "2_2") (pintype "passive"))
      (node (ref "R29") (pin "2") (pinfunction "2_2") (pintype "passive"))
      (node (ref "R3") (pin "2") (pinfunction "2_2") (pintype "passive"))
      (node (ref "U1") (pin "108") (pinfunction "GND_108") (pintype "power_in"))
      (node (ref "U1") (pin "113") (pinfunction "GND_113") (pintype "power_in"))
      (node (ref "U1") (pin "13") (pinfunction "GND_13") (pintype "passive"))
      (node (ref "U1") (pin "130") (pinfunction "GND_130") (pintype "passive"))
      (node (ref "U1") (pin "136") (pinfunction "GND_136") (pintype "passive"))
      (node (ref "U1") (pin "144") (pinfunction "IO_L1P_HSWAPEN_0_144") (pintype "bidirectional"))
      (node (ref "U1") (pin "25") (pinfunction "GND_25") (pintype "passive"))
      (node (ref "U1") (pin "3") (pinfunction "GND_3") (pintype "passive"))
      (node (ref "U1") (pin "49") (pinfunction "GND_49") (pintype "passive"))
      (node (ref "U1") (pin "54") (pinfunction "GND_54") (pintype "passive"))
      (node (ref "U1") (pin "60") (pinfunction "IO_L13P_M1_2_60") (pintype "bidirectional"))
      (node (ref "U1") (pin "68") (pinfunction "GND_68") (pintype "passive"))
      (node (ref "U1") (pin "73") (pinfunction "SUSPEND_73") (pintype "passive"))
      (node (ref "U1") (pin "77") (pinfunction "GND_77") (pintype "power_in"))
      (node (ref "U1") (pin "91") (pinfunction "GND_91") (pintype "power_in"))
      (node (ref "U1") (pin "96") (pinfunction "GND_96") (pintype "power_in"))
      (node (ref "U2") (pin "4") (pinfunction "GND_4") (pintype "power_in"))
      (node (ref "U3") (pin "12") (pinfunction "GND_12") (pintype "power_in"))
      (node (ref "U3") (pin "34") (pinfunction "GND_34") (pintype "power_in"))
      (node (ref "U3") (pin "37") (pinfunction "~{OE}_37") (pintype "input"))
      (node (ref "U3") (pin "8") (pinfunction "~{CE}_8") (pintype "input"))
      (node (ref "U4") (pin "12") (pinfunction "SELECT_12") (pintype "input"))
      (node (ref "U4") (pin "13") (pinfunction "DGND_13") (pintype "input"))
      (node (ref "U4") (pin "2") (pinfunction "AGND_2") (pintype "input"))
      (node (ref "U5") (pin "2") (pinfunction "VSS_2") (pintype "passive"))
      (node (ref "U6") (pin "1") (pinfunction "GND_1") (pintype "power_in"))
      (node (ref "U8") (pin "1") (pinfunction "GND_1") (pintype "power_in"))
    )
    (net (code "116") (name "Net-(C5-Pad1)") (class "Default")
      (node (ref "C5") (pin "1") (pinfunction "1_1") (pintype "passive"))
      (node (ref "R11") (pin "2") (pinfunction "2_2") (pintype "passive"))
    )
    (net (code "117") (name "Net-(C13-Pad2)") (class "Default")
      (node (ref "C13") (pin "2") (pinfunction "2_2") (pintype "passive"))
      (node (ref "R4") (pin "1") (pinfunction "1_1") (pintype "passive"))
    )
    (net (code "118") (name "Net-(D1-K)") (class "Default")
      (node (ref "C2") (pin "2") (pinfunction "2_2") (pintype "passive"))
      (node (ref "C5") (pin "2") (pinfunction "2_2") (pintype "passive"))
      (node (ref "D1") (pin "2") (pinfunction "K_2") (pintype "passive"))
      (node (ref "R28") (pin "1") (pinfunction "1_1") (pintype "passive"))
    )
    (net (code "119") (name "Net-(D2-A)") (class "Default")
      (node (ref "D2") (pin "1") (pinfunction "A_1") (pintype "passive"))
      (node (ref "R32") (pin "2") (pinfunction "2_2") (pintype "passive"))
      (node (ref "Y1") (pin "2") (pinfunction "2_2") (pintype "passive"))
    )
    (net (code "120") (name "Net-(D3-A)") (class "Default")
      (node (ref "D3") (pin "1") (pinfunction "A_1") (pintype "passive"))
      (node (ref "R33") (pin "1") (pinfunction "1_1") (pintype "passive"))
      (node (ref "Y2") (pin "2") (pinfunction "2_2") (pintype "passive"))
    )
    (net (code "121") (name "Net-(D4-ANODE)") (class "Default")
      (node (ref "D4") (pin "1") (pinfunction "ANODE_1") (pintype "passive"))
      (node (ref "R6") (pin "2") (pinfunction "2_2") (pintype "passive"))
    )
    (net (code "122") (name "Net-(D5-ANODE)") (class "Default")
      (node (ref "D5") (pin "1") (pinfunction "ANODE_1") (pintype "passive"))
      (node (ref "R7") (pin "2") (pinfunction "2_2") (pintype "passive"))
    )
    (net (code "123") (name "Net-(J1-Pad1)") (class "Default")
      (node (ref "J1") (pin "1") (pinfunction "1_1") (pintype "passive"))
      (node (ref "J12") (pin "1") (pinfunction "1_1") (pintype "passive"))
      (node (ref "J13") (pin "2") (pinfunction "2_2") (pintype "passive"))
    )
    (net (code "124") (name "Net-(J3-CENTER)") (class "Default")
      (node (ref "J3") (pin "1") (pinfunction "CENTER_1") (pintype "passive"))
      (node (ref "R4") (pin "2") (pinfunction "2_2") (pintype "passive"))
    )
    (net (code "125") (name "Net-(J5-A)") (class "Default")
      (node (ref "J5") (pin "4") (pinfunction "B_4") (pintype "passive"))
      (node (ref "J5") (pin "5") (pinfunction "A_5") (pintype "passive"))
      (node (ref "R11") (pin "1") (pinfunction "1_1") (pintype "passive"))
      (node (ref "R29") (pin "1") (pinfunction "1_1") (pintype "passive"))
    )
    (net (code "126") (name "Net-(J6-Pad7)") (class "Default")
      (node (ref "J6") (pin "7") (pinfunction "7_7") (pintype "passive"))
      (node (ref "R5") (pin "1") (pinfunction "1_1") (pintype "passive"))
    )
    (net (code "127") (name "Net-(J7-Pad1)") (class "Default")
      (node (ref "J7") (pin "1") (pinfunction "1_1") (pintype "passive"))
      (node (ref "R8") (pin "1") (pinfunction "1_1") (pintype "passive"))
    )
    (net (code "128") (name "Net-(J7-Pad2)") (class "Default")
      (node (ref "J7") (pin "2") (pinfunction "2_2") (pintype "passive"))
      (node (ref "R31") (pin "1") (pinfunction "1_1") (pintype "passive"))
    )
    (net (code "129") (name "Net-(J7-Pad5)") (class "Default")
      (node (ref "J7") (pin "5") (pinfunction "5_5") (pintype "passive"))
      (node (ref "R9") (pin "1") (pinfunction "1_1") (pintype "passive"))
    )
    (net (code "130") (name "Net-(J7-Pad6)") (class "Default")
      (node (ref "J7") (pin "6") (pinfunction "6_6") (pintype "passive"))
      (node (ref "R30") (pin "1") (pinfunction "1_1") (pintype "passive"))
    )
    (net (code "131") (name "Net-(J13-Pad1)") (class "Default")
      (node (ref "J13") (pin "1") (pinfunction "1_1") (pintype "passive"))
      (node (ref "L3") (pin "1") (pinfunction "1_1") (pintype "passive"))
    )
    (net (code "132") (name "Net-(Q1-BASE)") (class "Default")
      (node (ref "Q1") (pin "2") (pinfunction "BASE_2") (pintype "input"))
      (node (ref "R28") (pin "2") (pinfunction "2_2") (pintype "passive"))
    )
    (net (code "133") (name "Net-(U1-PROGRAM_B_2)") (class "Default")
      (node (ref "R24") (pin "1") (pinfunction "1_1") (pintype "passive"))
      (node (ref "U1") (pin "37") (pinfunction "PROGRAM_B_2_37") (pintype "passive"))
    )
    (net (code "134") (name "Net-(U4-BIN)") (class "Default")
      (node (ref "C6") (pin "2") (pinfunction "2_2") (pintype "passive"))
      (node (ref "U4") (pin "8") (pinfunction "BIN_8") (pintype "input"))
    )
    (net (code "135") (name "Net-(U4-CMPS)") (class "Default")
      (node (ref "C13") (pin "1") (pinfunction "1_1") (pintype "passive"))
      (node (ref "U4") (pin "10") (pinfunction "CMPS_10") (pintype "output"))
    )
    (net (code "136") (name "Net-(U4-FIN)") (class "Default")
      (node (ref "C1") (pin "1") (pinfunction "1_1") (pintype "passive"))
      (node (ref "U4") (pin "3") (pinfunction "FIN_3") (pintype "input"))
      (node (ref "Y1") (pin "1") (pinfunction "1_1") (pintype "passive"))
      (node (ref "Y2") (pin "1") (pinfunction "1_1") (pintype "passive"))
    )
    (net (code "137") (name "Net-(U4-GIN)") (class "Default")
      (node (ref "C7") (pin "2") (pinfunction "2_2") (pintype "passive"))
      (node (ref "U4") (pin "7") (pinfunction "GIN_7") (pintype "input"))
    )
    (net (code "138") (name "Net-(U4-RIN)") (class "Default")
      (node (ref "C8") (pin "2") (pinfunction "2_2") (pintype "passive"))
      (node (ref "U4") (pin "6") (pinfunction "RIN_6") (pintype "input"))
    )
    (net (code "139") (name "Net-(U6-TAB)") (class "Default")
      (node (ref "C15") (pin "1") (pinfunction "1_1") (pintype "passive"))
      (node (ref "L1") (pin "1") (pinfunction "1_1") (pintype "passive"))
      (node (ref "U6") (pin "2") (pinfunction "VOUT_2") (pintype "power_in"))
      (node (ref "U6") (pin "4") (pinfunction "TAB_4") (pintype "passive"))
    )
    (net (code "140") (name "Net-(U8-TAB)") (class "Default")
      (node (ref "C19") (pin "1") (pinfunction "1_1") (pintype "passive"))
      (node (ref "L2") (pin "1") (pinfunction "1_1") (pintype "passive"))
      (node (ref "U8") (pin "2") (pinfunction "VOUT_2") (pintype "power_in"))
      (node (ref "U8") (pin "4") (pinfunction "TAB_4") (pintype "passive"))
    )
    (net (code "141") (name "unconnected-(J5-C-Pad3)") (class "Default")
      (node (ref "J5") (pin "3") (pinfunction "C_3") (pintype "passive"))
    )
    (net (code "142") (name "unconnected-(J5-D-Pad2)") (class "Default")
      (node (ref "J5") (pin "2") (pinfunction "D_2") (pintype "passive"))
    )
    (net (code "143") (name "unconnected-(J6-Pad5)") (class "Default")
      (node (ref "J6") (pin "5") (pinfunction "5_5") (pintype "passive"))
    )
    (net (code "144") (name "unconnected-(J8-Pad1)") (class "Default")
      (node (ref "J8") (pin "1") (pinfunction "1_1") (pintype "passive"))
    )
    (net (code "145") (name "unconnected-(U1-CMPCS_B_2-Pad72)") (class "Default")
      (node (ref "U1") (pin "72") (pinfunction "CMPCS_B_2_72") (pintype "passive"))
    )
    (net (code "146") (name "unconnected-(U1-DONE_2-Pad71)") (class "Default")
      (node (ref "U1") (pin "71") (pinfunction "DONE_2_71") (pintype "passive"))
    )
    (net (code "147") (name "unconnected-(U4-CRMA-Pad9)") (class "Default")
      (node (ref "U4") (pin "9") (pinfunction "CRMA_9") (pintype "output"))
    )
    (net (code "148") (name "unconnected-(U4-LUMA-Pad11)") (class "Default")
      (node (ref "U4") (pin "11") (pinfunction "LUMA_11") (pintype "output"))
    )
    (net (code "149") (name "unconnected-(U5-E{slash}D-Pad1)") (class "Default")
      (node (ref "U5") (pin "1") (pinfunction "E/D_1") (pintype "output"))
    )
  )
)
